# Sheet1.net
KiCad netlist of a schematic drawn in Altium Designer
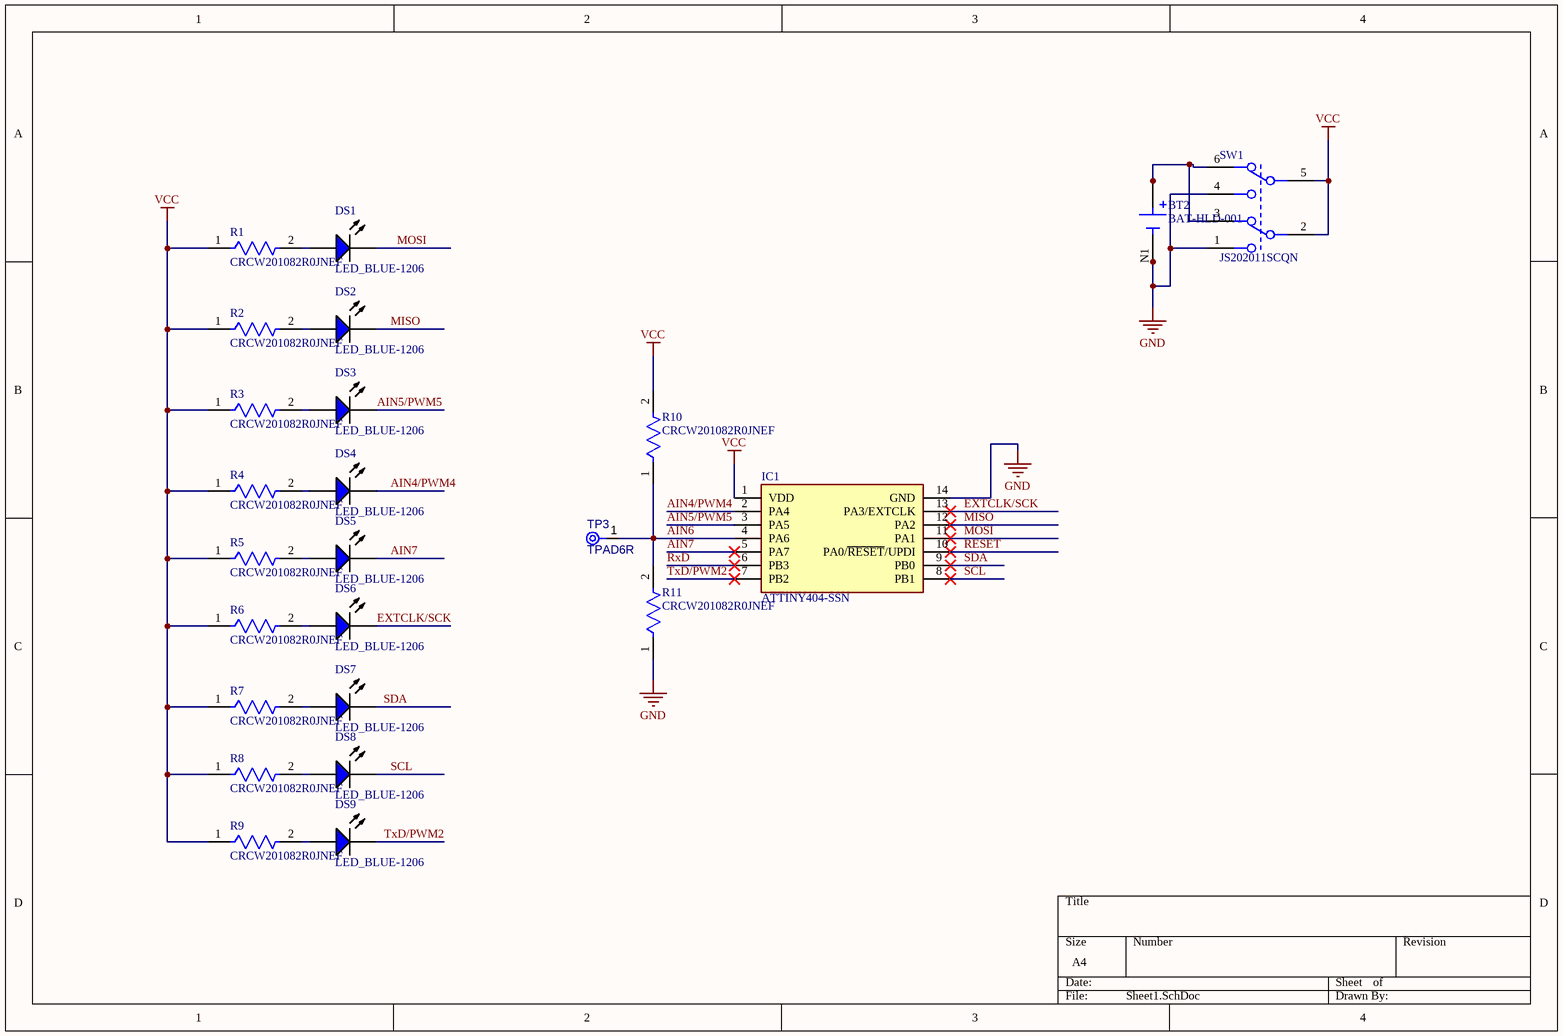
[diagram p0: Sheet1.SchDoc]

(export (version "E")
  (design (tool "Eeschema 10.0.6"))
  (components
    (comp (ref "BT2")
      (value "BAT-HLD-001")
      (footprint "BAT-HLD-001:BAT_BAT-HLD-001")
      (description "Battery Retainer Coin, 20.0mm 1 Cell SMD (SMT) Tab")
      (fields (field (name "MF") "{'manufacturer': u'Linx'}"))
      (libsource (lib "*") (part "BAT-HLD-001"))
    )
    (comp (ref "DS1")
      (value "LED_BLUE-1206")
      (footprint "LEDC3418X06M")
      (description "Generic LED in 1206 package")
      (libsource (lib "Test workspace") (part "LED-BLUE-AK-2"))
    )
    (comp (ref "DS2")
      (value "LED_BLUE-1206")
      (footprint "LEDC3418X06M")
      (description "Generic LED in 1206 package")
      (libsource (lib "Test workspace") (part "LED-BLUE-AK-2"))
    )
    (comp (ref "DS3")
      (value "LED_BLUE-1206")
      (footprint "LEDC3418X06M")
      (description "Generic LED in 1206 package")
      (libsource (lib "Test workspace") (part "LED-BLUE-AK-2"))
    )
    (comp (ref "DS4")
      (value "LED_BLUE-1206")
      (footprint "LEDC3418X06M")
      (description "Generic LED in 1206 package")
      (libsource (lib "Test workspace") (part "LED-BLUE-AK-2"))
    )
    (comp (ref "DS5")
      (value "LED_BLUE-1206")
      (footprint "LEDC3418X06M")
      (description "Generic LED in 1206 package")
      (libsource (lib "Test workspace") (part "LED-BLUE-AK-2"))
    )
    (comp (ref "DS6")
      (value "LED_BLUE-1206")
      (footprint "LEDC3418X06M")
      (description "Generic LED in 1206 package")
      (libsource (lib "Test workspace") (part "LED-BLUE-AK-2"))
    )
    (comp (ref "DS7")
      (value "LED_BLUE-1206")
      (footprint "LEDC3418X06M")
      (description "Generic LED in 1206 package")
      (libsource (lib "Test workspace") (part "LED-BLUE-AK-2"))
    )
    (comp (ref "DS8")
      (value "LED_BLUE-1206")
      (footprint "LEDC3418X06M")
      (description "Generic LED in 1206 package")
      (libsource (lib "Test workspace") (part "LED-BLUE-AK-2"))
    )
    (comp (ref "DS9")
      (value "LED_BLUE-1206")
      (footprint "LEDC3418X06M")
      (description "Generic LED in 1206 package")
      (libsource (lib "Test workspace") (part "LED-BLUE-AK-2"))
    )
    (comp (ref "IC1")
      (value "ATTINY404-SSN")
      (footprint "SamacSys:SOIC127P600X175-14N")
      (description "Integrated Circuit")
      (fields (field (name "MOUSER PART NUMBER") "579-ATTINY404-SSN"))
      (libsource (lib "*") (part "ATTINY404-SSN"))
    )
    (comp (ref "R1")
      (value "CRCW201082R0JNEF")
      (footprint "FP-CRCW2010-e3-IPC_A")
      (description "RES Thick Film, 82Ω, 5%, 0.75W, 200ppm/°C, 2010")
      (fields (field (name "TOLERANCE") "5%"))
      (libsource (lib "Altium Content Vault") (part "1029c3af85768c4190bb7ad29bc67b5"))
    )
    (comp (ref "R2")
      (value "CRCW201082R0JNEF")
      (footprint "FP-CRCW2010-e3-IPC_A")
      (description "RES Thick Film, 82Ω, 5%, 0.75W, 200ppm/°C, 2010")
      (fields (field (name "TOLERANCE") "5%"))
      (libsource (lib "Altium Content Vault") (part "1029c3af85768c4190bb7ad29bc67b5"))
    )
    (comp (ref "R3")
      (value "CRCW201082R0JNEF")
      (footprint "FP-CRCW2010-e3-IPC_A")
      (description "RES Thick Film, 82Ω, 5%, 0.75W, 200ppm/°C, 2010")
      (fields (field (name "TOLERANCE") "5%"))
      (libsource (lib "Altium Content Vault") (part "1029c3af85768c4190bb7ad29bc67b5"))
    )
    (comp (ref "R4")
      (value "CRCW201082R0JNEF")
      (footprint "FP-CRCW2010-e3-IPC_A")
      (description "RES Thick Film, 82Ω, 5%, 0.75W, 200ppm/°C, 2010")
      (fields (field (name "TOLERANCE") "5%"))
      (libsource (lib "Altium Content Vault") (part "1029c3af85768c4190bb7ad29bc67b5"))
    )
    (comp (ref "R5")
      (value "CRCW201082R0JNEF")
      (footprint "FP-CRCW2010-e3-IPC_A")
      (description "RES Thick Film, 82Ω, 5%, 0.75W, 200ppm/°C, 2010")
      (fields (field (name "TOLERANCE") "5%"))
      (libsource (lib "Altium Content Vault") (part "1029c3af85768c4190bb7ad29bc67b5"))
    )
    (comp (ref "R6")
      (value "CRCW201082R0JNEF")
      (footprint "FP-CRCW2010-e3-IPC_A")
      (description "RES Thick Film, 82Ω, 5%, 0.75W, 200ppm/°C, 2010")
      (fields (field (name "TOLERANCE") "5%"))
      (libsource (lib "Altium Content Vault") (part "1029c3af85768c4190bb7ad29bc67b5"))
    )
    (comp (ref "R7")
      (value "CRCW201082R0JNEF")
      (footprint "FP-CRCW2010-e3-IPC_A")
      (description "RES Thick Film, 82Ω, 5%, 0.75W, 200ppm/°C, 2010")
      (fields (field (name "TOLERANCE") "5%"))
      (libsource (lib "Altium Content Vault") (part "1029c3af85768c4190bb7ad29bc67b5"))
    )
    (comp (ref "R8")
      (value "CRCW201082R0JNEF")
      (footprint "FP-CRCW2010-e3-IPC_A")
      (description "RES Thick Film, 82Ω, 5%, 0.75W, 200ppm/°C, 2010")
      (fields (field (name "TOLERANCE") "5%"))
      (libsource (lib "Altium Content Vault") (part "1029c3af85768c4190bb7ad29bc67b5"))
    )
    (comp (ref "R9")
      (value "CRCW201082R0JNEF")
      (footprint "FP-CRCW2010-e3-IPC_A")
      (description "RES Thick Film, 82Ω, 5%, 0.75W, 200ppm/°C, 2010")
      (fields (field (name "TOLERANCE") "5%"))
      (libsource (lib "Altium Content Vault") (part "1029c3af85768c4190bb7ad29bc67b5"))
    )
    (comp (ref "R10")
      (value "CRCW201082R0JNEF")
      (footprint "FP-CRCW2010-e3-IPC_A")
      (description "RES Thick Film, 82Ω, 5%, 0.75W, 200ppm/°C, 2010")
      (fields (field (name "TOLERANCE") "5%"))
      (libsource (lib "Altium Content Vault") (part "1029c3af85768c4190bb7ad29bc67b5"))
    )
    (comp (ref "R11")
      (value "CRCW201082R0JNEF")
      (footprint "FP-CRCW2010-e3-IPC_A")
      (description "RES Thick Film, 82Ω, 5%, 0.75W, 200ppm/°C, 2010")
      (fields (field (name "TOLERANCE") "5%"))
      (libsource (lib "Altium Content Vault") (part "1029c3af85768c4190bb7ad29bc67b5"))
    )
    (comp (ref "SW1")
      (value "JS202011SCQN")
      (footprint "FP-JS202011SCQN-MFG")
      (description "SWITCH SLIDE DPDT 300MA 6V")
      (libsource (lib "Altium Content Vault") (part "ac99ea1af431c19115f5225061c5c88"))
    )
    (comp (ref "TP3")
      (value "TPAD6R")
      (footprint "TP06R")
      (description "0.6mm round")
      (libsource (lib "Test workspace") (part "CMP-001-0001-4"))
    )
  )
  (nets
    (net (code "1") (name "/AIN4{slash}PWM4") (class "Default")
      (node (ref "DS4") (pin "2") (pinfunction "K_2") (pintype "passive"))
      (node (ref "IC1") (pin "2") (pinfunction "PA4_2") (pintype "passive"))
    )
    (net (code "2") (name "/AIN5{slash}PWM5") (class "Default")
      (node (ref "DS3") (pin "2") (pinfunction "K_2") (pintype "passive"))
      (node (ref "IC1") (pin "3") (pinfunction "PA5_3") (pintype "passive"))
    )
    (net (code "3") (name "/AIN6") (class "Default")
      (node (ref "IC1") (pin "4") (pinfunction "PA6_4") (pintype "passive"))
      (node (ref "R10") (pin "1") (pinfunction "1_1") (pintype "passive"))
      (node (ref "R11") (pin "2") (pinfunction "2_2") (pintype "passive"))
      (node (ref "TP3") (pin "1") (pinfunction "TP_1") (pintype "passive"))
    )
    (net (code "4") (name "/AIN7") (class "Default")
      (node (ref "DS5") (pin "2") (pinfunction "K_2") (pintype "passive"))
      (node (ref "IC1") (pin "5") (pinfunction "PA7_5") (pintype "passive"))
    )
    (net (code "5") (name "/EXTCLK{slash}SCK") (class "Default")
      (node (ref "DS6") (pin "2") (pinfunction "K_2") (pintype "passive"))
      (node (ref "IC1") (pin "13") (pinfunction "PA3/EXTCLK_13") (pintype "passive"))
    )
    (net (code "6") (name "/MISO") (class "Default")
      (node (ref "DS2") (pin "2") (pinfunction "K_2") (pintype "passive"))
      (node (ref "IC1") (pin "12") (pinfunction "PA2_12") (pintype "passive"))
    )
    (net (code "7") (name "/MOSI") (class "Default")
      (node (ref "DS1") (pin "2") (pinfunction "K_2") (pintype "passive"))
      (node (ref "IC1") (pin "11") (pinfunction "PA1_11") (pintype "passive"))
    )
    (net (code "8") (name "/RESET") (class "Default")
      (node (ref "IC1") (pin "10") (pinfunction "PA0/~{RESET}/UPDI_10") (pintype "passive+no_connect"))
    )
    (net (code "9") (name "/RxD") (class "Default")
      (node (ref "IC1") (pin "6") (pinfunction "PB3_6") (pintype "passive+no_connect"))
    )
    (net (code "10") (name "/SCL") (class "Default")
      (node (ref "DS8") (pin "2") (pinfunction "K_2") (pintype "passive"))
      (node (ref "IC1") (pin "8") (pinfunction "PB1_8") (pintype "passive"))
    )
    (net (code "11") (name "/SDA") (class "Default")
      (node (ref "DS7") (pin "2") (pinfunction "K_2") (pintype "passive"))
      (node (ref "IC1") (pin "9") (pinfunction "PB0_9") (pintype "passive"))
    )
    (net (code "12") (name "/TxD{slash}PWM2") (class "Default")
      (node (ref "DS9") (pin "2") (pinfunction "K_2") (pintype "passive"))
      (node (ref "IC1") (pin "7") (pinfunction "PB2_7") (pintype "passive"))
    )
    (net (code "13") (name "GND") (class "Default")
      (node (ref "BT2") (pin "N1") (pinfunction "NEG_N1") (pintype "passive"))
      (node (ref "IC1") (pin "14") (pinfunction "GND_14") (pintype "passive"))
      (node (ref "R11") (pin "1") (pinfunction "1_1") (pintype "passive"))
      (node (ref "SW1") (pin "1") (pinfunction "1_1") (pintype "passive"))
      (node (ref "SW1") (pin "4") (pinfunction "4_4") (pintype "passive"))
    )
    (net (code "14") (name "Net-(BT2-POS-PadP1)") (class "Default")
      (node (ref "BT2") (pin "P1") (pinfunction "POS_P1") (pintype "passive"))
      (node (ref "BT2") (pin "P2") (pinfunction "POS_P2") (pintype "passive"))
      (node (ref "SW1") (pin "3") (pinfunction "3_3") (pintype "passive"))
      (node (ref "SW1") (pin "6") (pinfunction "6_6") (pintype "passive"))
    )
    (net (code "15") (name "Net-(DS1-A)") (class "Default")
      (node (ref "DS1") (pin "1") (pinfunction "A_1") (pintype "passive"))
      (node (ref "R1") (pin "2") (pinfunction "2_2") (pintype "passive"))
    )
    (net (code "16") (name "Net-(DS2-A)") (class "Default")
      (node (ref "DS2") (pin "1") (pinfunction "A_1") (pintype "passive"))
      (node (ref "R2") (pin "2") (pinfunction "2_2") (pintype "passive"))
    )
    (net (code "17") (name "Net-(DS3-A)") (class "Default")
      (node (ref "DS3") (pin "1") (pinfunction "A_1") (pintype "passive"))
      (node (ref "R3") (pin "2") (pinfunction "2_2") (pintype "passive"))
    )
    (net (code "18") (name "Net-(DS4-A)") (class "Default")
      (node (ref "DS4") (pin "1") (pinfunction "A_1") (pintype "passive"))
      (node (ref "R4") (pin "2") (pinfunction "2_2") (pintype "passive"))
    )
    (net (code "19") (name "Net-(DS5-A)") (class "Default")
      (node (ref "DS5") (pin "1") (pinfunction "A_1") (pintype "passive"))
      (node (ref "R5") (pin "2") (pinfunction "2_2") (pintype "passive"))
    )
    (net (code "20") (name "Net-(DS6-A)") (class "Default")
      (node (ref "DS6") (pin "1") (pinfunction "A_1") (pintype "passive"))
      (node (ref "R6") (pin "2") (pinfunction "2_2") (pintype "passive"))
    )
    (net (code "21") (name "Net-(DS7-A)") (class "Default")
      (node (ref "DS7") (pin "1") (pinfunction "A_1") (pintype "passive"))
      (node (ref "R7") (pin "2") (pinfunction "2_2") (pintype "passive"))
    )
    (net (code "22") (name "Net-(DS8-A)") (class "Default")
      (node (ref "DS8") (pin "1") (pinfunction "A_1") (pintype "passive"))
      (node (ref "R8") (pin "2") (pinfunction "2_2") (pintype "passive"))
    )
    (net (code "23") (name "Net-(DS9-A)") (class "Default")
      (node (ref "DS9") (pin "1") (pinfunction "A_1") (pintype "passive"))
      (node (ref "R9") (pin "2") (pinfunction "2_2") (pintype "passive"))
    )
    (net (code "24") (name "VCC") (class "Default")
      (node (ref "IC1") (pin "1") (pinfunction "VDD_1") (pintype "passive"))
      (node (ref "R1") (pin "1") (pinfunction "1_1") (pintype "passive"))
      (node (ref "R10") (pin "2") (pinfunction "2_2") (pintype "passive"))
      (node (ref "R2") (pin "1") (pinfunction "1_1") (pintype "passive"))
      (node (ref "R3") (pin "1") (pinfunction "1_1") (pintype "passive"))
      (node (ref "R4") (pin "1") (pinfunction "1_1") (pintype "passive"))
      (node (ref "R5") (pin "1") (pinfunction "1_1") (pintype "passive"))
      (node (ref "R6") (pin "1") (pinfunction "1_1") (pintype "passive"))
      (node (ref "R7") (pin "1") (pinfunction "1_1") (pintype "passive"))
      (node (ref "R8") (pin "1") (pinfunction "1_1") (pintype "passive"))
      (node (ref "R9") (pin "1") (pinfunction "1_1") (pintype "passive"))
      (node (ref "SW1") (pin "2") (pinfunction "2_2") (pintype "passive"))
      (node (ref "SW1") (pin "5") (pinfunction "5_5") (pintype "passive"))
    )
  )
)
